# Servo-SMD.net
KiCad netlist of a schematic drawn in EAGLE
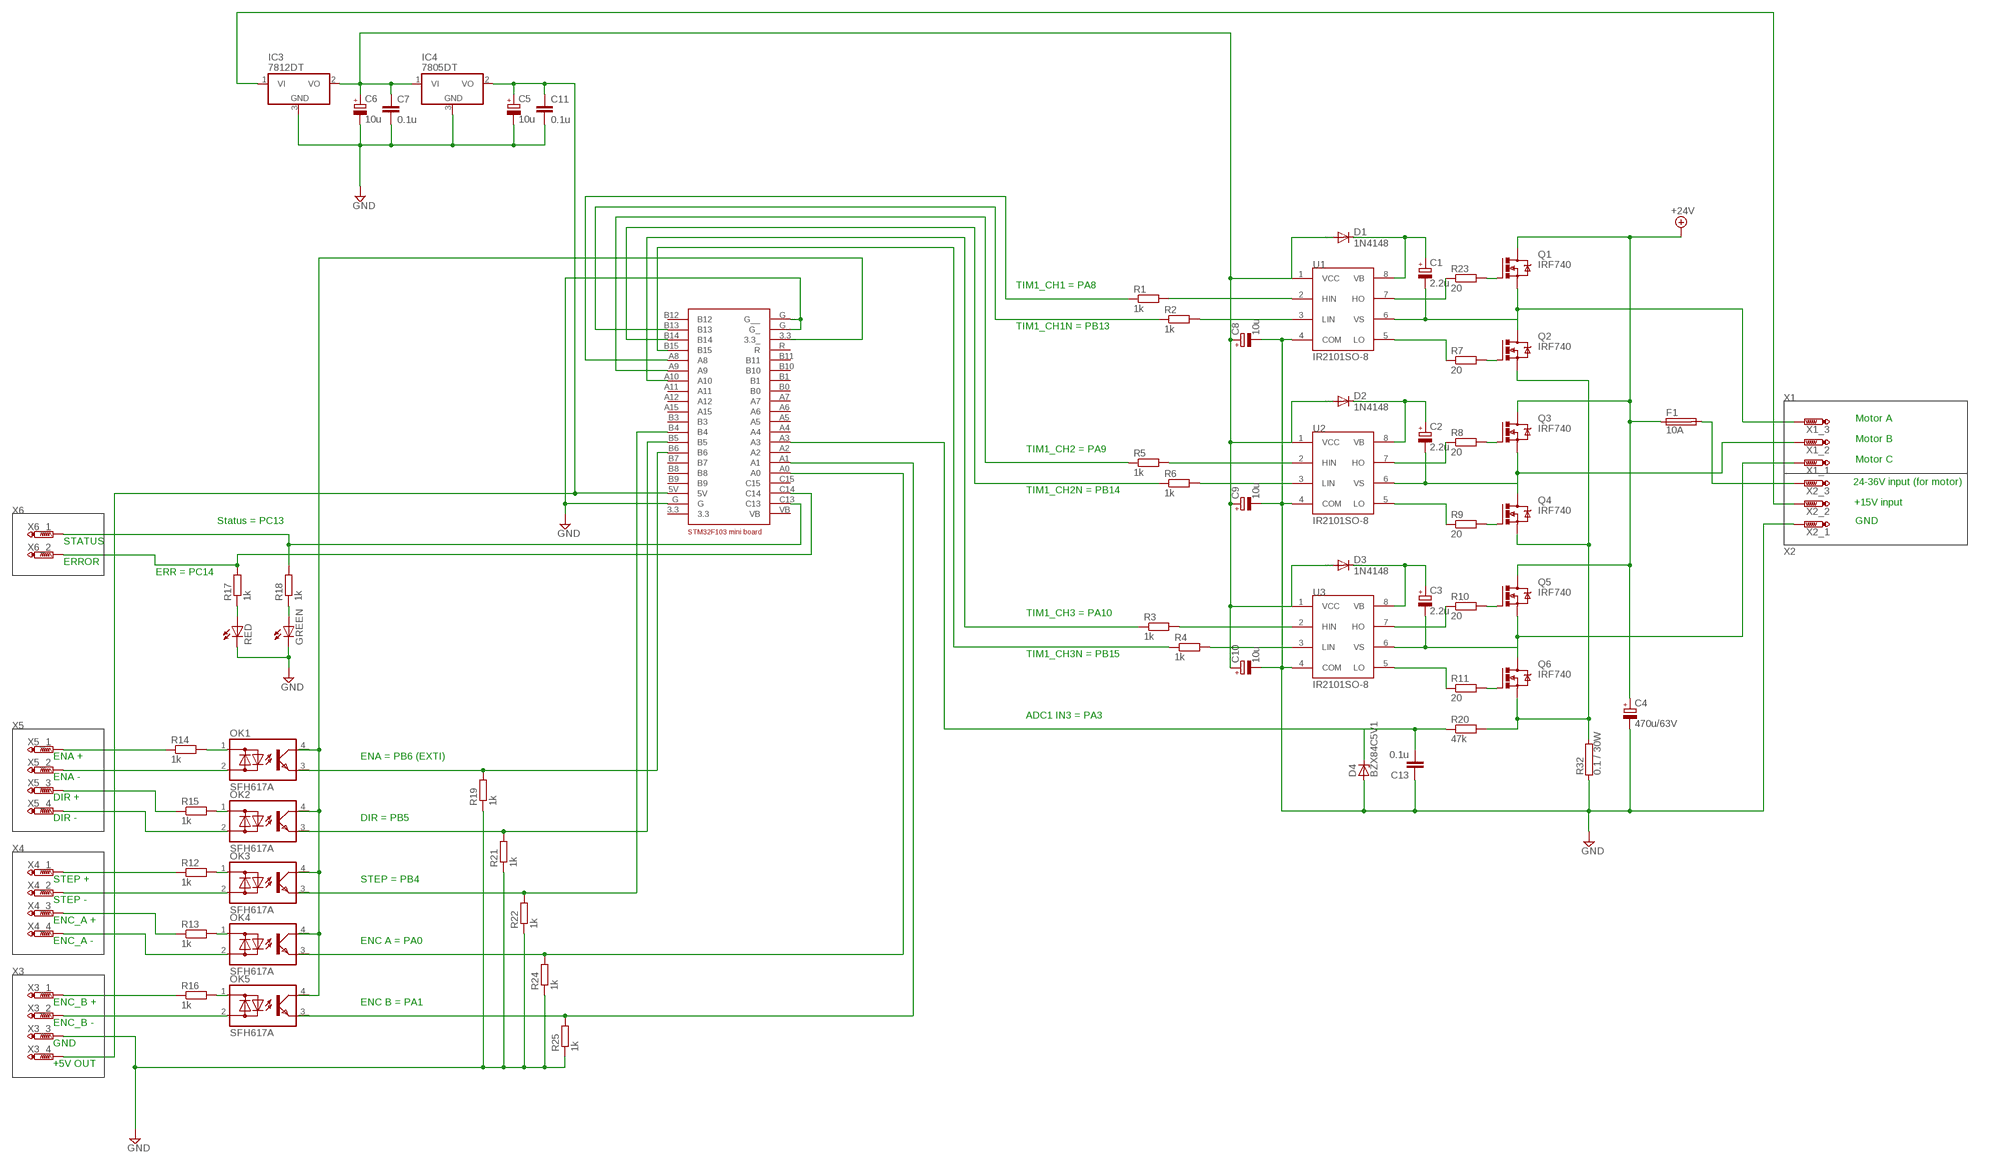
[diagram p0: schematic, sheet 1]

(export (version "E")
  (design (tool "Eeschema 10.0.6"))
  (components
    (comp (ref "C1")
      (value "2.2u")
      (footprint "eagle-import:SANYO-OSCON_SMD_C6")
      (libsource (lib "eagle-import") (part "CPOL-EUSANYO_SMD_C6"))
    )
    (comp (ref "C2")
      (value "2.2u")
      (footprint "eagle-import:SANYO-OSCON_SMD_C6")
      (libsource (lib "eagle-import") (part "CPOL-EUSANYO_SMD_C6"))
    )
    (comp (ref "C3")
      (value "2.2u")
      (footprint "eagle-import:SANYO-OSCON_SMD_C6")
      (libsource (lib "eagle-import") (part "CPOL-EUSANYO_SMD_C6"))
    )
    (comp (ref "C4")
      (value "470u/63V")
      (footprint "eagle-import:E5-13")
      (libsource (lib "eagle-import") (part "CPOL-EUE5-13"))
    )
    (comp (ref "C5")
      (value "10u")
      (footprint "eagle-import:SANYO-OSCON_SMD_C6")
      (libsource (lib "eagle-import") (part "CPOL-EUSANYO_SMD_C6"))
    )
    (comp (ref "C6")
      (value "10u")
      (footprint "eagle-import:SANYO-OSCON_SMD_C6")
      (libsource (lib "eagle-import") (part "CPOL-EUSANYO_SMD_C6"))
    )
    (comp (ref "C7")
      (value "0.1u")
      (footprint "eagle-import:C0805")
      (libsource (lib "eagle-import") (part "C-EUC0805"))
    )
    (comp (ref "C8")
      (value "10u")
      (footprint "eagle-import:SANYO-OSCON_SMD_C6")
      (libsource (lib "eagle-import") (part "CPOL-EUSANYO_SMD_C6"))
    )
    (comp (ref "C9")
      (value "10u")
      (footprint "eagle-import:SANYO-OSCON_SMD_C6")
      (libsource (lib "eagle-import") (part "CPOL-EUSANYO_SMD_C6"))
    )
    (comp (ref "C10")
      (value "10u")
      (footprint "eagle-import:SANYO-OSCON_SMD_C6")
      (libsource (lib "eagle-import") (part "CPOL-EUSANYO_SMD_C6"))
    )
    (comp (ref "C11")
      (value "0.1u")
      (footprint "eagle-import:C0805")
      (libsource (lib "eagle-import") (part "C-EUC0805"))
    )
    (comp (ref "C13")
      (value "0.1u")
      (footprint "eagle-import:C0805")
      (libsource (lib "eagle-import") (part "C-EUC0805"))
    )
    (comp (ref "D1")
      (value "1N4148")
      (footprint "eagle-import:SOD-123_MINI-SMA")
      (libsource (lib "eagle-import") (part "CGRM400-G1"))
    )
    (comp (ref "D2")
      (value "1N4148")
      (footprint "eagle-import:SOD-123_MINI-SMA")
      (libsource (lib "eagle-import") (part "CGRM400-G1"))
    )
    (comp (ref "D3")
      (value "1N4148")
      (footprint "eagle-import:SOD-123_MINI-SMA")
      (libsource (lib "eagle-import") (part "CGRM400-G1"))
    )
    (comp (ref "D4")
      (value "BZX84C5V1")
      (footprint "eagle-import:TO236")
      (libsource (lib "eagle-import") (part "BZX84CSMD"))
    )
    (comp (ref "F1")
      (value "10A")
      (footprint "eagle-import:SHK20L")
      (libsource (lib "eagle-import") (part "FUSESHK20L"))
    )
    (comp (ref "GREEN")
      (value "LEDSML0805")
      (footprint "eagle-import:SML0805")
      (libsource (lib "eagle-import") (part "LEDSML0805"))
    )
    (comp (ref "IC3")
      (value "7812DT")
      (footprint "eagle-import:TO252")
      (libsource (lib "eagle-import") (part "78DT05"))
    )
    (comp (ref "IC4")
      (value "7805DT")
      (footprint "eagle-import:TO252")
      (libsource (lib "eagle-import") (part "78DT12"))
    )
    (comp (ref "OK1")
      (value "SFH617A")
      (footprint "eagle-import:DIL4-SMD")
      (fields (field (name "MF") "VISHAY/TELEFUNKEN") (field (name "MPN") "SFH6206-3"))
      (libsource (lib "eagle-import") (part "SFH6206"))
    )
    (comp (ref "OK2")
      (value "SFH617A")
      (footprint "eagle-import:DIL4-SMD")
      (fields (field (name "MF") "VISHAY/TELEFUNKEN") (field (name "MPN") "SFH6206-3"))
      (libsource (lib "eagle-import") (part "SFH6206"))
    )
    (comp (ref "OK3")
      (value "SFH617A")
      (footprint "eagle-import:DIL4-SMD")
      (fields (field (name "MF") "VISHAY/TELEFUNKEN") (field (name "MPN") "SFH6206-3"))
      (libsource (lib "eagle-import") (part "SFH6206"))
    )
    (comp (ref "OK4")
      (value "SFH617A")
      (footprint "eagle-import:DIL4-SMD")
      (fields (field (name "MF") "VISHAY/TELEFUNKEN") (field (name "MPN") "SFH6206-3"))
      (libsource (lib "eagle-import") (part "SFH6206"))
    )
    (comp (ref "OK5")
      (value "SFH617A")
      (footprint "eagle-import:DIL4-SMD")
      (fields (field (name "MF") "VISHAY/TELEFUNKEN") (field (name "MPN") "SFH6206-3"))
      (libsource (lib "eagle-import") (part "SFH6206"))
    )
    (comp (ref "Q1")
      (value "IRF740")
      (footprint "eagle-import:TO220BV")
      (libsource (lib "eagle-import") (part "IRF740"))
    )
    (comp (ref "Q2")
      (value "IRF740")
      (footprint "eagle-import:TO220BV")
      (libsource (lib "eagle-import") (part "IRF740"))
    )
    (comp (ref "Q3")
      (value "IRF740")
      (footprint "eagle-import:TO220BV")
      (libsource (lib "eagle-import") (part "IRF740"))
    )
    (comp (ref "Q4")
      (value "IRF740")
      (footprint "eagle-import:TO220BV")
      (libsource (lib "eagle-import") (part "IRF740"))
    )
    (comp (ref "Q5")
      (value "IRF740")
      (footprint "eagle-import:TO220BV")
      (libsource (lib "eagle-import") (part "IRF740"))
    )
    (comp (ref "Q6")
      (value "IRF740")
      (footprint "eagle-import:TO220BV")
      (libsource (lib "eagle-import") (part "IRF740"))
    )
    (comp (ref "R1")
      (value "1k")
      (footprint "eagle-import:M0805")
      (libsource (lib "eagle-import") (part "resistor_R-EU_M0805"))
    )
    (comp (ref "R2")
      (value "1k")
      (footprint "eagle-import:M0805")
      (libsource (lib "eagle-import") (part "resistor_R-EU_M0805"))
    )
    (comp (ref "R3")
      (value "1k")
      (footprint "eagle-import:M0805")
      (libsource (lib "eagle-import") (part "resistor_R-EU_M0805"))
    )
    (comp (ref "R4")
      (value "1k")
      (footprint "eagle-import:M0805")
      (libsource (lib "eagle-import") (part "resistor_R-EU_M0805"))
    )
    (comp (ref "R5")
      (value "1k")
      (footprint "eagle-import:M0805")
      (libsource (lib "eagle-import") (part "resistor_R-EU_M0805"))
    )
    (comp (ref "R6")
      (value "1k")
      (footprint "eagle-import:M0805")
      (libsource (lib "eagle-import") (part "resistor_R-EU_M0805"))
    )
    (comp (ref "R7")
      (value "20")
      (footprint "eagle-import:M0805")
      (libsource (lib "eagle-import") (part "R-EU_M0805"))
    )
    (comp (ref "R8")
      (value "20")
      (footprint "eagle-import:M0805")
      (libsource (lib "eagle-import") (part "R-EU_M0805"))
    )
    (comp (ref "R9")
      (value "20")
      (footprint "eagle-import:M0805")
      (libsource (lib "eagle-import") (part "R-EU_M0805"))
    )
    (comp (ref "R10")
      (value "20")
      (footprint "eagle-import:M0805")
      (libsource (lib "eagle-import") (part "R-EU_M0805"))
    )
    (comp (ref "R11")
      (value "20")
      (footprint "eagle-import:M0805")
      (libsource (lib "eagle-import") (part "R-EU_M0805"))
    )
    (comp (ref "R12")
      (value "1k")
      (footprint "eagle-import:M0805")
      (libsource (lib "eagle-import") (part "resistor_R-EU_M0805"))
    )
    (comp (ref "R13")
      (value "1k")
      (footprint "eagle-import:M0805")
      (libsource (lib "eagle-import") (part "resistor_R-EU_M0805"))
    )
    (comp (ref "R14")
      (value "1k")
      (footprint "eagle-import:M0805")
      (libsource (lib "eagle-import") (part "resistor_R-EU_M0805"))
    )
    (comp (ref "R15")
      (value "1k")
      (footprint "eagle-import:M0805")
      (libsource (lib "eagle-import") (part "resistor_R-EU_M0805"))
    )
    (comp (ref "R16")
      (value "1k")
      (footprint "eagle-import:M0805")
      (libsource (lib "eagle-import") (part "resistor_R-EU_M0805"))
    )
    (comp (ref "R17")
      (value "1k")
      (footprint "eagle-import:M0805")
      (libsource (lib "eagle-import") (part "resistor_R-EU_M0805"))
    )
    (comp (ref "R18")
      (value "1k")
      (footprint "eagle-import:M0805")
      (libsource (lib "eagle-import") (part "resistor_R-EU_M0805"))
    )
    (comp (ref "R19")
      (value "1k")
      (footprint "eagle-import:M0805")
      (libsource (lib "eagle-import") (part "resistor_R-EU_M0805"))
    )
    (comp (ref "R20")
      (value "47k")
      (footprint "eagle-import:M0805")
      (libsource (lib "eagle-import") (part "resistor_R-EU_M0805"))
    )
    (comp (ref "R21")
      (value "1k")
      (footprint "eagle-import:M0805")
      (libsource (lib "eagle-import") (part "resistor_R-EU_M0805"))
    )
    (comp (ref "R22")
      (value "1k")
      (footprint "eagle-import:M0805")
      (libsource (lib "eagle-import") (part "resistor_R-EU_M0805"))
    )
    (comp (ref "R23")
      (value "20")
      (footprint "eagle-import:M0805")
      (libsource (lib "eagle-import") (part "R-EU_M0805"))
    )
    (comp (ref "R24")
      (value "1k")
      (footprint "eagle-import:M0805")
      (libsource (lib "eagle-import") (part "resistor_R-EU_M0805"))
    )
    (comp (ref "R25")
      (value "1k")
      (footprint "eagle-import:M0805")
      (libsource (lib "eagle-import") (part "resistor_R-EU_M0805"))
    )
    (comp (ref "R32")
      (value "0.1 / 30W")
      (footprint "eagle-import:TO220-2")
      (libsource (lib "eagle-import") (part "R"))
    )
    (comp (ref "RED")
      (value "LEDSML0805")
      (footprint "eagle-import:SML0805")
      (libsource (lib "eagle-import") (part "LEDSML0805"))
    )
    (comp (ref "U$1")
      (value "STM32F108")
      (footprint "eagle-import:STB32F108BRD")
      (libsource (lib "eagle-import") (part "STM32F108"))
    )
    (comp (ref "U1")
      (value "IR2101SO-8")
      (footprint "eagle-import:SO-8")
      (libsource (lib "eagle-import") (part "IR2101SO-8"))
    )
    (comp (ref "U2")
      (value "IR2101SO-8")
      (footprint "eagle-import:SO-8")
      (libsource (lib "eagle-import") (part "IR2101SO-8"))
    )
    (comp (ref "U3")
      (value "IR2101SO-8")
      (footprint "eagle-import:SO-8")
      (libsource (lib "eagle-import") (part "IR2101SO-8"))
    )
    (comp (ref "X1_1")
      (value "PTR1PAD1-13Y")
      (footprint "eagle-import:P1-13Y")
      (libsource (lib "eagle-import") (part "PTR1PAD1-13Y"))
    )
    (comp (ref "X1_2")
      (value "PTR1PAD1-13Y")
      (footprint "eagle-import:P1-13Y")
      (libsource (lib "eagle-import") (part "PTR1PAD1-13Y"))
    )
    (comp (ref "X1_3")
      (value "PTR1PAD1-13Y")
      (footprint "eagle-import:P1-13Y")
      (libsource (lib "eagle-import") (part "PTR1PAD1-13Y"))
    )
    (comp (ref "X2_1")
      (value "PTR1PAD1-13Y")
      (footprint "eagle-import:P1-13Y")
      (libsource (lib "eagle-import") (part "PTR1PAD1-13Y"))
    )
    (comp (ref "X2_2")
      (value "PTR1PAD1-13Y")
      (footprint "eagle-import:P1-13Y")
      (libsource (lib "eagle-import") (part "PTR1PAD1-13Y"))
    )
    (comp (ref "X2_3")
      (value "PTR1PAD1-13Y")
      (footprint "eagle-import:P1-13Y")
      (libsource (lib "eagle-import") (part "PTR1PAD1-13Y"))
    )
    (comp (ref "X3_1")
      (value "PTR1PAD1-13Y")
      (footprint "eagle-import:P1-13Y")
      (libsource (lib "eagle-import") (part "PTR1PAD1-13Y"))
    )
    (comp (ref "X3_2")
      (value "PTR1PAD1-13Y")
      (footprint "eagle-import:P1-13Y")
      (libsource (lib "eagle-import") (part "PTR1PAD1-13Y"))
    )
    (comp (ref "X3_3")
      (value "PTR1PAD1-13Y")
      (footprint "eagle-import:P1-13Y")
      (libsource (lib "eagle-import") (part "PTR1PAD1-13Y"))
    )
    (comp (ref "X3_4")
      (value "PTR1PAD1-13Y")
      (footprint "eagle-import:P1-13Y")
      (libsource (lib "eagle-import") (part "PTR1PAD1-13Y"))
    )
    (comp (ref "X4_1")
      (value "PTR1PAD1-13Y")
      (footprint "eagle-import:P1-13Y")
      (libsource (lib "eagle-import") (part "PTR1PAD1-13Y"))
    )
    (comp (ref "X4_2")
      (value "PTR1PAD1-13Y")
      (footprint "eagle-import:P1-13Y")
      (libsource (lib "eagle-import") (part "PTR1PAD1-13Y"))
    )
    (comp (ref "X4_3")
      (value "PTR1PAD1-13Y")
      (footprint "eagle-import:P1-13Y")
      (libsource (lib "eagle-import") (part "PTR1PAD1-13Y"))
    )
    (comp (ref "X4_4")
      (value "PTR1PAD1-13Y")
      (footprint "eagle-import:P1-13Y")
      (libsource (lib "eagle-import") (part "PTR1PAD1-13Y"))
    )
    (comp (ref "X5_1")
      (value "PTR1PAD1-13Y")
      (footprint "eagle-import:P1-13Y")
      (libsource (lib "eagle-import") (part "PTR1PAD1-13Y"))
    )
    (comp (ref "X5_2")
      (value "PTR1PAD1-13Y")
      (footprint "eagle-import:P1-13Y")
      (libsource (lib "eagle-import") (part "PTR1PAD1-13Y"))
    )
    (comp (ref "X5_3")
      (value "PTR1PAD1-13Y")
      (footprint "eagle-import:P1-13Y")
      (libsource (lib "eagle-import") (part "PTR1PAD1-13Y"))
    )
    (comp (ref "X5_4")
      (value "PTR1PAD1-13Y")
      (footprint "eagle-import:P1-13Y")
      (libsource (lib "eagle-import") (part "PTR1PAD1-13Y"))
    )
    (comp (ref "X6_1")
      (value "PTR1PAD1-13Y")
      (footprint "eagle-import:P1-13Y")
      (libsource (lib "eagle-import") (part "PTR1PAD1-13Y"))
    )
    (comp (ref "X6_2")
      (value "PTR1PAD1-13Y")
      (footprint "eagle-import:P1-13Y")
      (libsource (lib "eagle-import") (part "PTR1PAD1-13Y"))
    )
  )
  (nets
    (net (code "1") (name "+24V") (class "Default")
      (node (ref "C4") (pin "+") (pinfunction "+_+") (pintype "passive"))
      (node (ref "F1") (pin "1A") (pinfunction "1_1A") (pintype "passive"))
      (node (ref "Q1") (pin "D") (pinfunction "D_D") (pintype "passive"))
      (node (ref "Q3") (pin "D") (pinfunction "D_D") (pintype "passive"))
      (node (ref "Q5") (pin "D") (pinfunction "D_D") (pintype "passive"))
    )
    (net (code "2") (name "GND") (class "Default")
      (node (ref "C10") (pin "-") (pinfunction "-_-") (pintype "passive"))
      (node (ref "C11") (pin "2") (pinfunction "2_2") (pintype "passive"))
      (node (ref "C13") (pin "1") (pinfunction "1_1") (pintype "passive"))
      (node (ref "C4") (pin "-") (pinfunction "-_-") (pintype "passive"))
      (node (ref "C5") (pin "-") (pinfunction "-_-") (pintype "passive"))
      (node (ref "C6") (pin "-") (pinfunction "-_-") (pintype "passive"))
      (node (ref "C7") (pin "2") (pinfunction "2_2") (pintype "passive"))
      (node (ref "C8") (pin "-") (pinfunction "-_-") (pintype "passive"))
      (node (ref "C9") (pin "-") (pinfunction "-_-") (pintype "passive"))
      (node (ref "D4") (pin "A") (pinfunction "A_A") (pintype "passive"))
      (node (ref "GREEN") (pin "C") (pinfunction "C_C") (pintype "passive"))
      (node (ref "IC3") (pin "3") (pinfunction "GND_3") (pintype "passive"))
      (node (ref "IC4") (pin "3") (pinfunction "GND_3") (pintype "passive"))
      (node (ref "R19") (pin "1") (pinfunction "1_1") (pintype "passive"))
      (node (ref "R21") (pin "1") (pinfunction "1_1") (pintype "passive"))
      (node (ref "R22") (pin "1") (pinfunction "1_1") (pintype "passive"))
      (node (ref "R24") (pin "1") (pinfunction "1_1") (pintype "passive"))
      (node (ref "R25") (pin "1") (pinfunction "1_1") (pintype "passive"))
      (node (ref "R32") (pin "P$1") (pinfunction "1_P$1") (pintype "passive"))
      (node (ref "RED") (pin "C") (pinfunction "C_C") (pintype "passive"))
      (node (ref "U$1") (pin "G") (pinfunction "G_G") (pintype "bidirectional"))
      (node (ref "U$1") (pin "G_") (pinfunction "G__G_") (pintype "bidirectional"))
      (node (ref "U$1") (pin "G__") (pinfunction "G___G__") (pintype "bidirectional"))
      (node (ref "U1") (pin "4") (pinfunction "COM_4") (pintype "power_in"))
      (node (ref "U2") (pin "4") (pinfunction "COM_4") (pintype "power_in"))
      (node (ref "U3") (pin "4") (pinfunction "COM_4") (pintype "power_in"))
      (node (ref "X2_1") (pin "TP") (pinfunction "TP_TP") (pintype "input"))
      (node (ref "X3_3") (pin "TP") (pinfunction "TP_TP") (pintype "input"))
    )
    (net (code "3") (name "Net-(C13-Pad2)") (class "Default")
      (node (ref "C13") (pin "2") (pinfunction "2_2") (pintype "passive"))
      (node (ref "D4") (pin "C") (pinfunction "C_C") (pintype "passive"))
      (node (ref "R20") (pin "1") (pinfunction "1_1") (pintype "passive"))
      (node (ref "U$1") (pin "A3") (pinfunction "A3_A3") (pintype "bidirectional"))
    )
    (net (code "4") (name "Net-(F1-2)") (class "Default")
      (node (ref "F1") (pin "2A") (pinfunction "2_2A") (pintype "passive"))
      (node (ref "X2_3") (pin "TP") (pinfunction "TP_TP") (pintype "input"))
    )
    (net (code "5") (name "Net-(GREEN-PadA)") (class "Default")
      (node (ref "GREEN") (pin "A") (pinfunction "A_A") (pintype "passive"))
      (node (ref "R18") (pin "1") (pinfunction "1_1") (pintype "passive"))
    )
    (net (code "6") (name "Net-(IC3-VI)") (class "Default")
      (node (ref "IC3") (pin "1") (pinfunction "VI_1") (pintype "input"))
      (node (ref "X2_2") (pin "TP") (pinfunction "TP_TP") (pintype "input"))
    )
    (net (code "7") (name "Net-(IC3-VO)") (class "Default")
      (node (ref "C10") (pin "+") (pinfunction "+_+") (pintype "passive"))
      (node (ref "C6") (pin "+") (pinfunction "+_+") (pintype "passive"))
      (node (ref "C7") (pin "1") (pinfunction "1_1") (pintype "passive"))
      (node (ref "C8") (pin "+") (pinfunction "+_+") (pintype "passive"))
      (node (ref "C9") (pin "+") (pinfunction "+_+") (pintype "passive"))
      (node (ref "D1") (pin "A") (pinfunction "A_A") (pintype "passive"))
      (node (ref "D2") (pin "A") (pinfunction "A_A") (pintype "passive"))
      (node (ref "D3") (pin "A") (pinfunction "A_A") (pintype "passive"))
      (node (ref "IC3") (pin "2") (pinfunction "VO_2") (pintype "passive"))
      (node (ref "IC4") (pin "1") (pinfunction "VI_1") (pintype "input"))
      (node (ref "U1") (pin "1") (pinfunction "VCC_1") (pintype "power_in"))
      (node (ref "U2") (pin "1") (pinfunction "VCC_1") (pintype "power_in"))
      (node (ref "U3") (pin "1") (pinfunction "VCC_1") (pintype "power_in"))
    )
    (net (code "8") (name "Net-(IC4-VO)") (class "Default")
      (node (ref "C11") (pin "1") (pinfunction "1_1") (pintype "passive"))
      (node (ref "C5") (pin "+") (pinfunction "+_+") (pintype "passive"))
      (node (ref "IC4") (pin "2") (pinfunction "VO_2") (pintype "passive"))
      (node (ref "U$1") (pin "5V") (pinfunction "5V_5V") (pintype "bidirectional"))
      (node (ref "X3_4") (pin "TP") (pinfunction "TP_TP") (pintype "input"))
    )
    (net (code "9") (name "Net-(OK1-AC1)") (class "Default")
      (node (ref "OK1") (pin "1") (pinfunction "AC1_1") (pintype "passive"))
      (node (ref "R14") (pin "2") (pinfunction "2_2") (pintype "passive"))
    )
    (net (code "10") (name "Net-(OK1-AC2)") (class "Default")
      (node (ref "OK1") (pin "2") (pinfunction "AC2_2") (pintype "passive"))
      (node (ref "X5_2") (pin "TP") (pinfunction "TP_TP") (pintype "input"))
    )
    (net (code "11") (name "Net-(OK1-C)") (class "Default")
      (node (ref "OK1") (pin "4") (pinfunction "C_4") (pintype "passive"))
      (node (ref "OK2") (pin "4") (pinfunction "C_4") (pintype "passive"))
      (node (ref "OK3") (pin "4") (pinfunction "C_4") (pintype "passive"))
      (node (ref "OK4") (pin "4") (pinfunction "C_4") (pintype "passive"))
      (node (ref "OK5") (pin "4") (pinfunction "C_4") (pintype "passive"))
      (node (ref "U$1") (pin "3.3_") (pinfunction "3.3__3.3_") (pintype "bidirectional"))
    )
    (net (code "12") (name "Net-(OK1-E)") (class "Default")
      (node (ref "OK1") (pin "3") (pinfunction "E_3") (pintype "passive"))
      (node (ref "R19") (pin "2") (pinfunction "2_2") (pintype "passive"))
      (node (ref "U$1") (pin "B6") (pinfunction "B6_B6") (pintype "bidirectional"))
    )
    (net (code "13") (name "Net-(OK2-AC1)") (class "Default")
      (node (ref "OK2") (pin "1") (pinfunction "AC1_1") (pintype "passive"))
      (node (ref "R15") (pin "2") (pinfunction "2_2") (pintype "passive"))
    )
    (net (code "14") (name "Net-(OK2-AC2)") (class "Default")
      (node (ref "OK2") (pin "2") (pinfunction "AC2_2") (pintype "passive"))
      (node (ref "X5_4") (pin "TP") (pinfunction "TP_TP") (pintype "input"))
    )
    (net (code "15") (name "Net-(OK2-E)") (class "Default")
      (node (ref "OK2") (pin "3") (pinfunction "E_3") (pintype "passive"))
      (node (ref "R21") (pin "2") (pinfunction "2_2") (pintype "passive"))
      (node (ref "U$1") (pin "B5") (pinfunction "B5_B5") (pintype "bidirectional"))
    )
    (net (code "16") (name "Net-(OK3-AC1)") (class "Default")
      (node (ref "OK3") (pin "1") (pinfunction "AC1_1") (pintype "passive"))
      (node (ref "R12") (pin "2") (pinfunction "2_2") (pintype "passive"))
    )
    (net (code "17") (name "Net-(OK3-AC2)") (class "Default")
      (node (ref "OK3") (pin "2") (pinfunction "AC2_2") (pintype "passive"))
      (node (ref "X4_2") (pin "TP") (pinfunction "TP_TP") (pintype "input"))
    )
    (net (code "18") (name "Net-(OK3-E)") (class "Default")
      (node (ref "OK3") (pin "3") (pinfunction "E_3") (pintype "passive"))
      (node (ref "R22") (pin "2") (pinfunction "2_2") (pintype "passive"))
      (node (ref "U$1") (pin "B4") (pinfunction "B4_B4") (pintype "bidirectional"))
    )
    (net (code "19") (name "Net-(OK4-AC1)") (class "Default")
      (node (ref "OK4") (pin "1") (pinfunction "AC1_1") (pintype "passive"))
      (node (ref "R13") (pin "2") (pinfunction "2_2") (pintype "passive"))
    )
    (net (code "20") (name "Net-(OK4-AC2)") (class "Default")
      (node (ref "OK4") (pin "2") (pinfunction "AC2_2") (pintype "passive"))
      (node (ref "X4_4") (pin "TP") (pinfunction "TP_TP") (pintype "input"))
    )
    (net (code "21") (name "Net-(OK4-E)") (class "Default")
      (node (ref "OK4") (pin "3") (pinfunction "E_3") (pintype "passive"))
      (node (ref "R24") (pin "2") (pinfunction "2_2") (pintype "passive"))
      (node (ref "U$1") (pin "A0") (pinfunction "A0_A0") (pintype "bidirectional"))
    )
    (net (code "22") (name "Net-(OK5-AC1)") (class "Default")
      (node (ref "OK5") (pin "1") (pinfunction "AC1_1") (pintype "passive"))
      (node (ref "R16") (pin "2") (pinfunction "2_2") (pintype "passive"))
    )
    (net (code "23") (name "Net-(OK5-AC2)") (class "Default")
      (node (ref "OK5") (pin "2") (pinfunction "AC2_2") (pintype "passive"))
      (node (ref "X3_2") (pin "TP") (pinfunction "TP_TP") (pintype "input"))
    )
    (net (code "24") (name "Net-(OK5-E)") (class "Default")
      (node (ref "OK5") (pin "3") (pinfunction "E_3") (pintype "passive"))
      (node (ref "R25") (pin "2") (pinfunction "2_2") (pintype "passive"))
      (node (ref "U$1") (pin "A1") (pinfunction "A1_A1") (pintype "bidirectional"))
    )
    (net (code "25") (name "Net-(Q1-PadG)") (class "Default")
      (node (ref "Q1") (pin "G") (pinfunction "G_G") (pintype "passive"))
      (node (ref "R23") (pin "2") (pinfunction "2_2") (pintype "passive"))
    )
    (net (code "26") (name "Net-(Q2-PadG)") (class "Default")
      (node (ref "Q2") (pin "G") (pinfunction "G_G") (pintype "passive"))
      (node (ref "R7") (pin "2") (pinfunction "2_2") (pintype "passive"))
    )
    (net (code "27") (name "Net-(Q3-PadG)") (class "Default")
      (node (ref "Q3") (pin "G") (pinfunction "G_G") (pintype "passive"))
      (node (ref "R8") (pin "2") (pinfunction "2_2") (pintype "passive"))
    )
    (net (code "28") (name "Net-(Q4-PadG)") (class "Default")
      (node (ref "Q4") (pin "G") (pinfunction "G_G") (pintype "passive"))
      (node (ref "R9") (pin "2") (pinfunction "2_2") (pintype "passive"))
    )
    (net (code "29") (name "Net-(Q5-PadG)") (class "Default")
      (node (ref "Q5") (pin "G") (pinfunction "G_G") (pintype "passive"))
      (node (ref "R10") (pin "2") (pinfunction "2_2") (pintype "passive"))
    )
    (net (code "30") (name "Net-(Q6-PadG)") (class "Default")
      (node (ref "Q6") (pin "G") (pinfunction "G_G") (pintype "passive"))
      (node (ref "R11") (pin "2") (pinfunction "2_2") (pintype "passive"))
    )
    (net (code "31") (name "Net-(R1-Pad1)") (class "Default")
      (node (ref "R1") (pin "1") (pinfunction "1_1") (pintype "passive"))
      (node (ref "U$1") (pin "A8") (pinfunction "A8_A8") (pintype "bidirectional"))
    )
    (net (code "32") (name "Net-(R2-Pad1)") (class "Default")
      (node (ref "R2") (pin "1") (pinfunction "1_1") (pintype "passive"))
      (node (ref "U$1") (pin "B13") (pinfunction "B13_B13") (pintype "bidirectional"))
    )
    (net (code "33") (name "Net-(R3-Pad1)") (class "Default")
      (node (ref "R3") (pin "1") (pinfunction "1_1") (pintype "passive"))
      (node (ref "U$1") (pin "A10") (pinfunction "A10_A10") (pintype "bidirectional"))
    )
    (net (code "34") (name "Net-(R4-Pad1)") (class "Default")
      (node (ref "R4") (pin "1") (pinfunction "1_1") (pintype "passive"))
      (node (ref "U$1") (pin "B15") (pinfunction "B15_B15") (pintype "bidirectional"))
    )
    (net (code "35") (name "Net-(R5-Pad1)") (class "Default")
      (node (ref "R5") (pin "1") (pinfunction "1_1") (pintype "passive"))
      (node (ref "U$1") (pin "A9") (pinfunction "A9_A9") (pintype "bidirectional"))
    )
    (net (code "36") (name "Net-(R6-Pad1)") (class "Default")
      (node (ref "R6") (pin "1") (pinfunction "1_1") (pintype "passive"))
      (node (ref "U$1") (pin "B14") (pinfunction "B14_B14") (pintype "bidirectional"))
    )
    (net (code "37") (name "Net-(R12-Pad1)") (class "Default")
      (node (ref "R12") (pin "1") (pinfunction "1_1") (pintype "passive"))
      (node (ref "X4_1") (pin "TP") (pinfunction "TP_TP") (pintype "input"))
    )
    (net (code "38") (name "Net-(R13-Pad1)") (class "Default")
      (node (ref "R13") (pin "1") (pinfunction "1_1") (pintype "passive"))
      (node (ref "X4_3") (pin "TP") (pinfunction "TP_TP") (pintype "input"))
    )
    (net (code "39") (name "Net-(R14-Pad1)") (class "Default")
      (node (ref "R14") (pin "1") (pinfunction "1_1") (pintype "passive"))
      (node (ref "X5_1") (pin "TP") (pinfunction "TP_TP") (pintype "input"))
    )
    (net (code "40") (name "Net-(R15-Pad1)") (class "Default")
      (node (ref "R15") (pin "1") (pinfunction "1_1") (pintype "passive"))
      (node (ref "X5_3") (pin "TP") (pinfunction "TP_TP") (pintype "input"))
    )
    (net (code "41") (name "Net-(R16-Pad1)") (class "Default")
      (node (ref "R16") (pin "1") (pinfunction "1_1") (pintype "passive"))
      (node (ref "X3_1") (pin "TP") (pinfunction "TP_TP") (pintype "input"))
    )
    (net (code "42") (name "Net-(R17-Pad1)") (class "Default")
      (node (ref "R17") (pin "1") (pinfunction "1_1") (pintype "passive"))
      (node (ref "RED") (pin "A") (pinfunction "A_A") (pintype "passive"))
    )
    (net (code "43") (name "Net-(R17-Pad2)") (class "Default")
      (node (ref "R17") (pin "2") (pinfunction "2_2") (pintype "passive"))
      (node (ref "U$1") (pin "C14") (pinfunction "C14_C14") (pintype "bidirectional"))
      (node (ref "X6_2") (pin "TP") (pinfunction "TP_TP") (pintype "input"))
    )
    (net (code "44") (name "Net-(R18-Pad2)") (class "Default")
      (node (ref "R18") (pin "2") (pinfunction "2_2") (pintype "passive"))
      (node (ref "U$1") (pin "C13") (pinfunction "C13_C13") (pintype "bidirectional"))
      (node (ref "X6_1") (pin "TP") (pinfunction "TP_TP") (pintype "input"))
    )
    (net (code "45") (name "Net-(R32-2)") (class "Default")
      (node (ref "Q2") (pin "S") (pinfunction "S_S") (pintype "passive"))
      (node (ref "Q4") (pin "S") (pinfunction "S_S") (pintype "passive"))
      (node (ref "Q6") (pin "S") (pinfunction "S_S") (pintype "passive"))
      (node (ref "R20") (pin "2") (pinfunction "2_2") (pintype "passive"))
      (node (ref "R32") (pin "P$2") (pinfunction "2_P$2") (pintype "passive"))
    )
    (net (code "46") (name "Net-(U1-HIN)") (class "Default")
      (node (ref "R1") (pin "2") (pinfunction "2_2") (pintype "passive"))
      (node (ref "U1") (pin "2") (pinfunction "HIN_2") (pintype "input"))
    )
    (net (code "47") (name "Net-(U1-HO)") (class "Default")
      (node (ref "R23") (pin "1") (pinfunction "1_1") (pintype "passive"))
      (node (ref "U1") (pin "7") (pinfunction "HO_7") (pintype "output"))
    )
    (net (code "48") (name "Net-(U1-LIN)") (class "Default")
      (node (ref "R2") (pin "2") (pinfunction "2_2") (pintype "passive"))
      (node (ref "U1") (pin "3") (pinfunction "LIN_3") (pintype "input"))
    )
    (net (code "49") (name "Net-(U1-LO)") (class "Default")
      (node (ref "R7") (pin "1") (pinfunction "1_1") (pintype "passive"))
      (node (ref "U1") (pin "5") (pinfunction "LO_5") (pintype "output"))
    )
    (net (code "50") (name "Net-(U1-VB)") (class "Default")
      (node (ref "C1") (pin "+") (pinfunction "+_+") (pintype "passive"))
      (node (ref "D1") (pin "C") (pinfunction "C_C") (pintype "passive"))
      (node (ref "U1") (pin "8") (pinfunction "VB_8") (pintype "power_in"))
    )
    (net (code "51") (name "Net-(U1-VS)") (class "Default")
      (node (ref "C1") (pin "-") (pinfunction "-_-") (pintype "passive"))
      (node (ref "Q1") (pin "S") (pinfunction "S_S") (pintype "passive"))
      (node (ref "Q2") (pin "D") (pinfunction "D_D") (pintype "passive"))
      (node (ref "U1") (pin "6") (pinfunction "VS_6") (pintype "output"))
      (node (ref "X1_3") (pin "TP") (pinfunction "TP_TP") (pintype "input"))
    )
    (net (code "52") (name "Net-(U2-HIN)") (class "Default")
      (node (ref "R5") (pin "2") (pinfunction "2_2") (pintype "passive"))
      (node (ref "U2") (pin "2") (pinfunction "HIN_2") (pintype "input"))
    )
    (net (code "53") (name "Net-(U2-HO)") (class "Default")
      (node (ref "R8") (pin "1") (pinfunction "1_1") (pintype "passive"))
      (node (ref "U2") (pin "7") (pinfunction "HO_7") (pintype "output"))
    )
    (net (code "54") (name "Net-(U2-LIN)") (class "Default")
      (node (ref "R6") (pin "2") (pinfunction "2_2") (pintype "passive"))
      (node (ref "U2") (pin "3") (pinfunction "LIN_3") (pintype "input"))
    )
    (net (code "55") (name "Net-(U2-LO)") (class "Default")
      (node (ref "R9") (pin "1") (pinfunction "1_1") (pintype "passive"))
      (node (ref "U2") (pin "5") (pinfunction "LO_5") (pintype "output"))
    )
    (net (code "56") (name "Net-(U2-VB)") (class "Default")
      (node (ref "C2") (pin "+") (pinfunction "+_+") (pintype "passive"))
      (node (ref "D2") (pin "C") (pinfunction "C_C") (pintype "passive"))
      (node (ref "U2") (pin "8") (pinfunction "VB_8") (pintype "power_in"))
    )
    (net (code "57") (name "Net-(U2-VS)") (class "Default")
      (node (ref "C2") (pin "-") (pinfunction "-_-") (pintype "passive"))
      (node (ref "Q3") (pin "S") (pinfunction "S_S") (pintype "passive"))
      (node (ref "Q4") (pin "D") (pinfunction "D_D") (pintype "passive"))
      (node (ref "U2") (pin "6") (pinfunction "VS_6") (pintype "output"))
      (node (ref "X1_2") (pin "TP") (pinfunction "TP_TP") (pintype "input"))
    )
    (net (code "58") (name "Net-(U3-HIN)") (class "Default")
      (node (ref "R3") (pin "2") (pinfunction "2_2") (pintype "passive"))
      (node (ref "U3") (pin "2") (pinfunction "HIN_2") (pintype "input"))
    )
    (net (code "59") (name "Net-(U3-HO)") (class "Default")
      (node (ref "R10") (pin "1") (pinfunction "1_1") (pintype "passive"))
      (node (ref "U3") (pin "7") (pinfunction "HO_7") (pintype "output"))
    )
    (net (code "60") (name "Net-(U3-LIN)") (class "Default")
      (node (ref "R4") (pin "2") (pinfunction "2_2") (pintype "passive"))
      (node (ref "U3") (pin "3") (pinfunction "LIN_3") (pintype "input"))
    )
    (net (code "61") (name "Net-(U3-LO)") (class "Default")
      (node (ref "R11") (pin "1") (pinfunction "1_1") (pintype "passive"))
      (node (ref "U3") (pin "5") (pinfunction "LO_5") (pintype "output"))
    )
    (net (code "62") (name "Net-(U3-VB)") (class "Default")
      (node (ref "C3") (pin "+") (pinfunction "+_+") (pintype "passive"))
      (node (ref "D3") (pin "C") (pinfunction "C_C") (pintype "passive"))
      (node (ref "U3") (pin "8") (pinfunction "VB_8") (pintype "power_in"))
    )
    (net (code "63") (name "Net-(U3-VS)") (class "Default")
      (node (ref "C3") (pin "-") (pinfunction "-_-") (pintype "passive"))
      (node (ref "Q5") (pin "S") (pinfunction "S_S") (pintype "passive"))
      (node (ref "Q6") (pin "D") (pinfunction "D_D") (pintype "passive"))
      (node (ref "U3") (pin "6") (pinfunction "VS_6") (pintype "output"))
      (node (ref "X1_1") (pin "TP") (pinfunction "TP_TP") (pintype "input"))
    )
    (net (code "64") (name "unconnected-(U$1-Pad3.3)") (class "Default")
      (node (ref "U$1") (pin "3.3") (pinfunction "3.3_3.3") (pintype "bidirectional"))
    )
    (net (code "65") (name "unconnected-(U$1-PadA2)") (class "Default")
      (node (ref "U$1") (pin "A2") (pinfunction "A2_A2") (pintype "bidirectional"))
    )
    (net (code "66") (name "unconnected-(U$1-PadA4)") (class "Default")
      (node (ref "U$1") (pin "A4") (pinfunction "A4_A4") (pintype "bidirectional"))
    )
    (net (code "67") (name "unconnected-(U$1-PadA5)") (class "Default")
      (node (ref "U$1") (pin "A5") (pinfunction "A5_A5") (pintype "bidirectional"))
    )
    (net (code "68") (name "unconnected-(U$1-PadA6)") (class "Default")
      (node (ref "U$1") (pin "A6") (pinfunction "A6_A6") (pintype "bidirectional"))
    )
    (net (code "69") (name "unconnected-(U$1-PadA7)") (class "Default")
      (node (ref "U$1") (pin "A7") (pinfunction "A7_A7") (pintype "bidirectional"))
    )
    (net (code "70") (name "unconnected-(U$1-PadA11)") (class "Default")
      (node (ref "U$1") (pin "A11") (pinfunction "A11_A11") (pintype "bidirectional"))
    )
    (net (code "71") (name "unconnected-(U$1-PadA12)") (class "Default")
      (node (ref "U$1") (pin "A12") (pinfunction "A12_A12") (pintype "bidirectional"))
    )
    (net (code "72") (name "unconnected-(U$1-PadA15)") (class "Default")
      (node (ref "U$1") (pin "A15") (pinfunction "A15_A15") (pintype "bidirectional"))
    )
    (net (code "73") (name "unconnected-(U$1-PadB0)") (class "Default")
      (node (ref "U$1") (pin "B0") (pinfunction "B0_B0") (pintype "bidirectional"))
    )
    (net (code "74") (name "unconnected-(U$1-PadB1)") (class "Default")
      (node (ref "U$1") (pin "B1") (pinfunction "B1_B1") (pintype "bidirectional"))
    )
    (net (code "75") (name "unconnected-(U$1-PadB3)") (class "Default")
      (node (ref "U$1") (pin "B3") (pinfunction "B3_B3") (pintype "bidirectional"))
    )
    (net (code "76") (name "unconnected-(U$1-PadB7)") (class "Default")
      (node (ref "U$1") (pin "B7") (pinfunction "B7_B7") (pintype "bidirectional"))
    )
    (net (code "77") (name "unconnected-(U$1-PadB8)") (class "Default")
      (node (ref "U$1") (pin "B8") (pinfunction "B8_B8") (pintype "bidirectional"))
    )
    (net (code "78") (name "unconnected-(U$1-PadB9)") (class "Default")
      (node (ref "U$1") (pin "B9") (pinfunction "B9_B9") (pintype "bidirectional"))
    )
    (net (code "79") (name "unconnected-(U$1-PadB10)") (class "Default")
      (node (ref "U$1") (pin "B10") (pinfunction "B10_B10") (pintype "bidirectional"))
    )
    (net (code "80") (name "unconnected-(U$1-PadB11)") (class "Default")
      (node (ref "U$1") (pin "B11") (pinfunction "B11_B11") (pintype "bidirectional"))
    )
    (net (code "81") (name "unconnected-(U$1-PadB12)") (class "Default")
      (node (ref "U$1") (pin "B12") (pinfunction "B12_B12") (pintype "bidirectional"))
    )
    (net (code "82") (name "unconnected-(U$1-PadC15)") (class "Default")
      (node (ref "U$1") (pin "C15") (pinfunction "C15_C15") (pintype "bidirectional"))
    )
    (net (code "83") (name "unconnected-(U$1-PadR)") (class "Default")
      (node (ref "U$1") (pin "R") (pinfunction "R_R") (pintype "bidirectional"))
    )
    (net (code "84") (name "unconnected-(U$1-PadVB)") (class "Default")
      (node (ref "U$1") (pin "VB") (pinfunction "VB_VB") (pintype "bidirectional"))
    )
  )
)
